# standalone_temp_controller.net
KiCad netlist of a schematic drawn in EAGLE
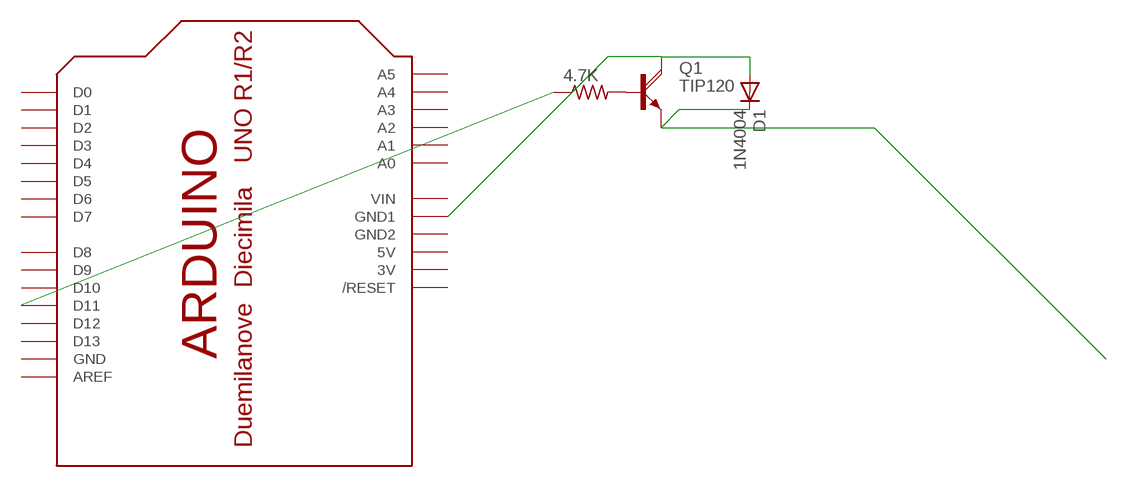
[diagram p0: schematic, sheet 1]

(export (version "E")
  (design (tool "Eeschema 10.0.6"))
  (components
    (comp (ref "4.7K")
      (value "R-US_0204/7")
      (footprint "eagle-import:0204_7")
      (libsource (lib "eagle-import") (part "R-US_0204/7"))
    )
    (comp (ref "D1")
      (value "1N4004")
      (footprint "eagle-import:DO41-10")
      (libsource (lib "eagle-import") (part "1N4004"))
    )
    (comp (ref "Q1")
      (value "TIP120")
      (footprint "eagle-import:TO220AH")
      (libsource (lib "eagle-import") (part "TIP120"))
    )
    (comp (ref "U$1")
      (value "ARDUINOUNO")
      (footprint "eagle-import:ARDUINO")
      (libsource (lib "eagle-import") (part "ARDUINOUNO"))
    )
  )
  (nets
    (net (code "1") (name "/3V") (class "Default")
      (node (ref "U$1") (pin "3V") (pinfunction "3V_3V") (pintype "power_in"))
    )
    (net (code "2") (name "/5V") (class "Default")
      (node (ref "U$1") (pin "5V") (pinfunction "5V_5V") (pintype "power_in"))
    )
    (net (code "3") (name "/GND") (class "Default")
      (node (ref "U$1") (pin "GND") (pinfunction "GND_GND") (pintype "power_in"))
    )
    (net (code "4") (name "/GND2") (class "Default")
      (node (ref "U$1") (pin "GND2") (pinfunction "GND2_GND2") (pintype "power_in"))
    )
    (net (code "5") (name "/VIN") (class "Default")
      (node (ref "U$1") (pin "VIN") (pinfunction "VIN_VIN") (pintype "power_in"))
    )
    (net (code "6") (name "Net-(4.7K-Pad1)") (class "Default")
      (node (ref "4.7K") (pin "1") (pinfunction "1_1") (pintype "passive"))
      (node (ref "U$1") (pin "D11") (pinfunction "D11_D11") (pintype "bidirectional"))
    )
    (net (code "7") (name "Net-(4.7K-Pad2)") (class "Default")
      (node (ref "4.7K") (pin "2") (pinfunction "2_2") (pintype "passive"))
      (node (ref "Q1") (pin "B") (pinfunction "B_B") (pintype "passive"))
    )
    (net (code "8") (name "Net-(D1-PadA)") (class "Default")
      (node (ref "D1") (pin "A") (pinfunction "A_A") (pintype "passive"))
      (node (ref "Q1") (pin "C") (pinfunction "C_C") (pintype "passive"))
      (node (ref "U$1") (pin "GND1") (pinfunction "GND1_GND1") (pintype "power_in"))
    )
    (net (code "9") (name "Net-(D1-PadC)") (class "Default")
      (node (ref "D1") (pin "C") (pinfunction "C_C") (pintype "passive"))
      (node (ref "Q1") (pin "E") (pinfunction "E_E") (pintype "passive"))
    )
    (net (code "10") (name "unconnected-(U$1-PadA0)") (class "Default")
      (node (ref "U$1") (pin "A0") (pinfunction "A0_A0") (pintype "bidirectional"))
    )
    (net (code "11") (name "unconnected-(U$1-PadA1)") (class "Default")
      (node (ref "U$1") (pin "A1") (pinfunction "A1_A1") (pintype "bidirectional"))
    )
    (net (code "12") (name "unconnected-(U$1-PadA2)") (class "Default")
      (node (ref "U$1") (pin "A2") (pinfunction "A2_A2") (pintype "bidirectional"))
    )
    (net (code "13") (name "unconnected-(U$1-PadA3)") (class "Default")
      (node (ref "U$1") (pin "A3") (pinfunction "A3_A3") (pintype "bidirectional"))
    )
    (net (code "14") (name "unconnected-(U$1-PadA4)") (class "Default")
      (node (ref "U$1") (pin "A4") (pinfunction "A4_A4") (pintype "bidirectional"))
    )
    (net (code "15") (name "unconnected-(U$1-PadA5)") (class "Default")
      (node (ref "U$1") (pin "A5") (pinfunction "A5_A5") (pintype "bidirectional"))
    )
    (net (code "16") (name "unconnected-(U$1-PadAREF)") (class "Default")
      (node (ref "U$1") (pin "AREF") (pinfunction "AREF_AREF") (pintype "bidirectional"))
    )
    (net (code "17") (name "unconnected-(U$1-PadD0)") (class "Default")
      (node (ref "U$1") (pin "D0") (pinfunction "D0_D0") (pintype "bidirectional"))
    )
    (net (code "18") (name "unconnected-(U$1-PadD1)") (class "Default")
      (node (ref "U$1") (pin "D1") (pinfunction "D1_D1") (pintype "bidirectional"))
    )
    (net (code "19") (name "unconnected-(U$1-PadD2)") (class "Default")
      (node (ref "U$1") (pin "D2") (pinfunction "D2_D2") (pintype "bidirectional"))
    )
    (net (code "20") (name "unconnected-(U$1-PadD3)") (class "Default")
      (node (ref "U$1") (pin "D3") (pinfunction "D3_D3") (pintype "bidirectional"))
    )
    (net (code "21") (name "unconnected-(U$1-PadD4)") (class "Default")
      (node (ref "U$1") (pin "D4") (pinfunction "D4_D4") (pintype "bidirectional"))
    )
    (net (code "22") (name "unconnected-(U$1-PadD5)") (class "Default")
      (node (ref "U$1") (pin "D5") (pinfunction "D5_D5") (pintype "bidirectional"))
    )
    (net (code "23") (name "unconnected-(U$1-PadD6)") (class "Default")
      (node (ref "U$1") (pin "D6") (pinfunction "D6_D6") (pintype "bidirectional"))
    )
    (net (code "24") (name "unconnected-(U$1-PadD7)") (class "Default")
      (node (ref "U$1") (pin "D7") (pinfunction "D7_D7") (pintype "bidirectional"))
    )
    (net (code "25") (name "unconnected-(U$1-PadD8)") (class "Default")
      (node (ref "U$1") (pin "D8") (pinfunction "D8_D8") (pintype "bidirectional"))
    )
    (net (code "26") (name "unconnected-(U$1-PadD9)") (class "Default")
      (node (ref "U$1") (pin "D9") (pinfunction "D9_D9") (pintype "bidirectional"))
    )
    (net (code "27") (name "unconnected-(U$1-PadD10)") (class "Default")
      (node (ref "U$1") (pin "D10") (pinfunction "D10_D10") (pintype "bidirectional"))
    )
    (net (code "28") (name "unconnected-(U$1-PadD12)") (class "Default")
      (node (ref "U$1") (pin "D12") (pinfunction "D12_D12") (pintype "bidirectional"))
    )
    (net (code "29") (name "unconnected-(U$1-PadD13)") (class "Default")
      (node (ref "U$1") (pin "D13") (pinfunction "D13_D13") (pintype "bidirectional"))
    )
    (net (code "30") (name "unconnected-(U$1-{slash}RESET-PadRESET)") (class "Default")
      (node (ref "U$1") (pin "RESET") (pinfunction "/RESET_RESET") (pintype "bidirectional"))
    )
  )
)
